# Bridge_rectifier.net
KiCad netlist of a schematic drawn in EAGLE
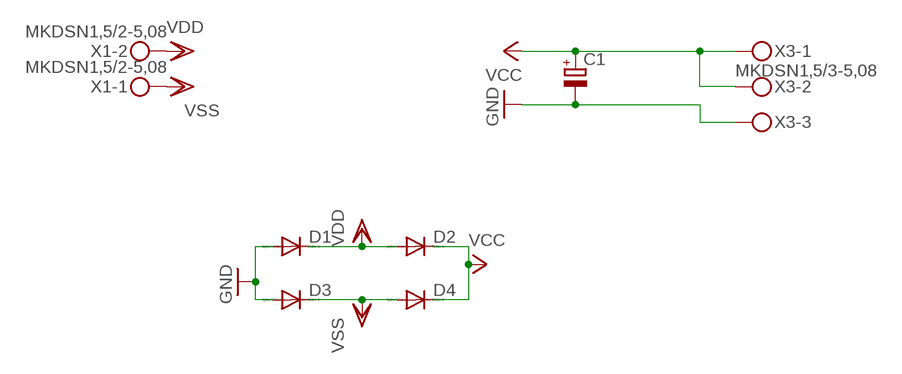
[diagram p0: schematic, sheet 1]

(export (version "E")
  (design (tool "Eeschema 10.0.6"))
  (components
    (comp (ref "C1")
      (value "CPOL-EUE2.5-7")
      (footprint "eagle-import:E2,5-7")
      (libsource (lib "eagle-import") (part "CPOL-EUE2.5-7"))
    )
    (comp (ref "D1")
      (value "DIODE-DO-214AC")
      (footprint "eagle-import:DO-214AC")
      (libsource (lib "eagle-import") (part "DIODE-DO-214AC"))
    )
    (comp (ref "D2")
      (value "DIODE-DO-214AC")
      (footprint "eagle-import:DO-214AC")
      (libsource (lib "eagle-import") (part "DIODE-DO-214AC"))
    )
    (comp (ref "D3")
      (value "DIODE-DO-214AC")
      (footprint "eagle-import:DO-214AC")
      (libsource (lib "eagle-import") (part "DIODE-DO-214AC"))
    )
    (comp (ref "D4")
      (value "DIODE-DO-214AC")
      (footprint "eagle-import:DO-214AC")
      (libsource (lib "eagle-import") (part "DIODE-DO-214AC"))
    )
    (comp (ref "X1")
      (value "MKDSN1,5/2-5,08")
      (footprint "eagle-import:MKDSN1,5_2-5,08")
      (libsource (lib "eagle-import") (part "MKDSN1,5/2-5,08"))
    )
    (comp (ref "X3")
      (value "MKDSN1,5/3-5,08")
      (footprint "eagle-import:MKDSN1,5_3-5,08")
      (libsource (lib "eagle-import") (part "MKDSN1,5/3-5,08"))
    )
  )
  (nets
    (net (code "1") (name "GND") (class "Default")
      (node (ref "C1") (pin "-") (pinfunction "-_-") (pintype "passive"))
      (node (ref "D1") (pin "A") (pinfunction "A_A") (pintype "passive"))
      (node (ref "D3") (pin "A") (pinfunction "A_A") (pintype "passive"))
      (node (ref "X3") (pin "3") (pinfunction "KL_3") (pintype "passive"))
    )
    (net (code "2") (name "VCC") (class "Default")
      (node (ref "C1") (pin "+") (pinfunction "+_+") (pintype "passive"))
      (node (ref "D2") (pin "C") (pinfunction "C_C") (pintype "passive"))
      (node (ref "D4") (pin "C") (pinfunction "C_C") (pintype "passive"))
      (node (ref "X3") (pin "1") (pinfunction "KL_1") (pintype "passive"))
      (node (ref "X3") (pin "2") (pinfunction "KL_2") (pintype "passive"))
    )
    (net (code "3") (name "VDD") (class "Default")
      (node (ref "D1") (pin "C") (pinfunction "C_C") (pintype "passive"))
      (node (ref "D2") (pin "A") (pinfunction "A_A") (pintype "passive"))
      (node (ref "X1") (pin "2") (pinfunction "KL_2") (pintype "passive"))
    )
    (net (code "4") (name "VSS") (class "Default")
      (node (ref "D3") (pin "C") (pinfunction "C_C") (pintype "passive"))
      (node (ref "D4") (pin "A") (pinfunction "A_A") (pintype "passive"))
      (node (ref "X1") (pin "1") (pinfunction "KL_1") (pintype "passive"))
    )
  )
)
